# RESISTORS_OLD.net
KiCad netlist of a schematic drawn in Altium Designer
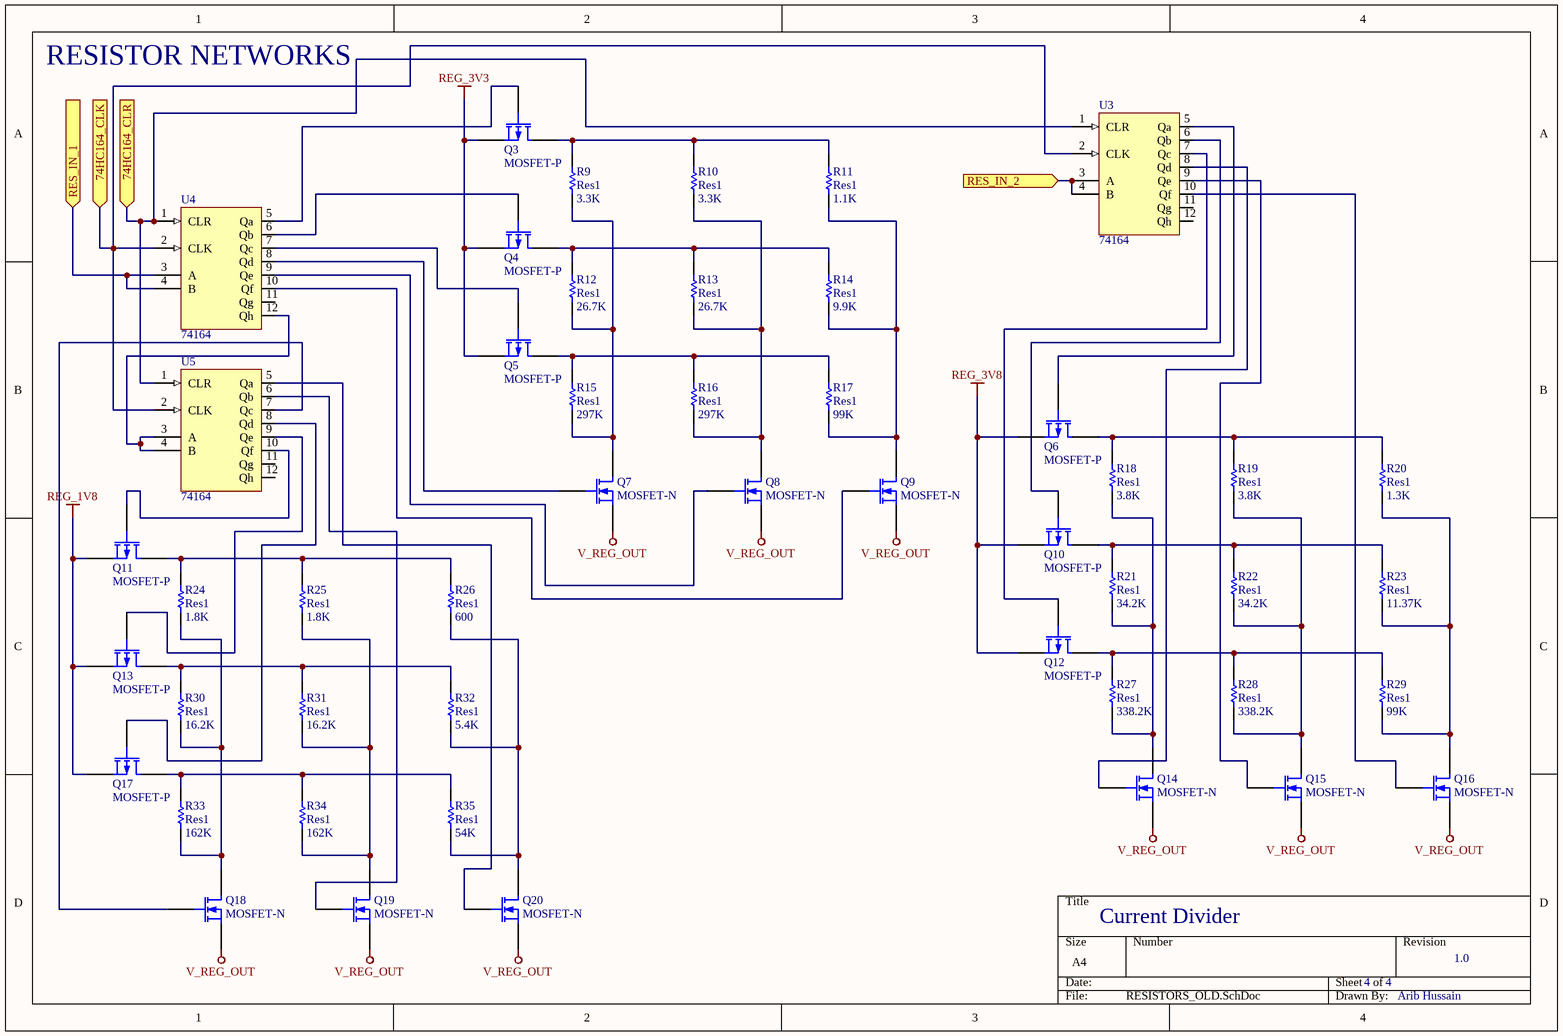
[diagram p0: RESISTORS_OLD.SchDoc]

(export (version "E")
  (design (tool "Eeschema 10.0.6"))
  (components
    (comp (ref "Q3")
      (value "MOSFET-P")
      (footprint "E3")
      (description "P-Channel MOSFET")
      (fields (field (name "PUBLISHER") "Altium Limited"))
      (libsource (lib "Miscellaneous Devices") (part "MOSFET-P"))
    )
    (comp (ref "Q4")
      (value "MOSFET-P")
      (footprint "E3")
      (description "P-Channel MOSFET")
      (fields (field (name "PUBLISHER") "Altium Limited"))
      (libsource (lib "Miscellaneous Devices") (part "MOSFET-P"))
    )
    (comp (ref "Q5")
      (value "MOSFET-P")
      (footprint "E3")
      (description "P-Channel MOSFET")
      (fields (field (name "PUBLISHER") "Altium Limited"))
      (libsource (lib "Miscellaneous Devices") (part "MOSFET-P"))
    )
    (comp (ref "Q6")
      (value "MOSFET-P")
      (footprint "E3")
      (description "P-Channel MOSFET")
      (fields (field (name "PUBLISHER") "Altium Limited"))
      (libsource (lib "Miscellaneous Devices") (part "MOSFET-P"))
    )
    (comp (ref "Q7")
      (value "MOSFET-N")
      (footprint "E3")
      (description "N-Channel MOSFET")
      (fields (field (name "PUBLISHER") "Altium Limited"))
      (libsource (lib "Miscellaneous Devices") (part "MOSFET-N"))
    )
    (comp (ref "Q8")
      (value "MOSFET-N")
      (footprint "E3")
      (description "N-Channel MOSFET")
      (fields (field (name "PUBLISHER") "Altium Limited"))
      (libsource (lib "Miscellaneous Devices") (part "MOSFET-N"))
    )
    (comp (ref "Q9")
      (value "MOSFET-N")
      (footprint "E3")
      (description "N-Channel MOSFET")
      (fields (field (name "PUBLISHER") "Altium Limited"))
      (libsource (lib "Miscellaneous Devices") (part "MOSFET-N"))
    )
    (comp (ref "Q10")
      (value "MOSFET-P")
      (footprint "E3")
      (description "P-Channel MOSFET")
      (fields (field (name "PUBLISHER") "Altium Limited"))
      (libsource (lib "Miscellaneous Devices") (part "MOSFET-P"))
    )
    (comp (ref "Q11")
      (value "MOSFET-P")
      (footprint "E3")
      (description "P-Channel MOSFET")
      (fields (field (name "PUBLISHER") "Altium Limited"))
      (libsource (lib "Miscellaneous Devices") (part "MOSFET-P"))
    )
    (comp (ref "Q12")
      (value "MOSFET-P")
      (footprint "E3")
      (description "P-Channel MOSFET")
      (fields (field (name "PUBLISHER") "Altium Limited"))
      (libsource (lib "Miscellaneous Devices") (part "MOSFET-P"))
    )
    (comp (ref "Q13")
      (value "MOSFET-P")
      (footprint "E3")
      (description "P-Channel MOSFET")
      (fields (field (name "PUBLISHER") "Altium Limited"))
      (libsource (lib "Miscellaneous Devices") (part "MOSFET-P"))
    )
    (comp (ref "Q14")
      (value "MOSFET-N")
      (footprint "E3")
      (description "N-Channel MOSFET")
      (fields (field (name "PUBLISHER") "Altium Limited"))
      (libsource (lib "Miscellaneous Devices") (part "MOSFET-N"))
    )
    (comp (ref "Q15")
      (value "MOSFET-N")
      (footprint "E3")
      (description "N-Channel MOSFET")
      (fields (field (name "PUBLISHER") "Altium Limited"))
      (libsource (lib "Miscellaneous Devices") (part "MOSFET-N"))
    )
    (comp (ref "Q16")
      (value "MOSFET-N")
      (footprint "E3")
      (description "N-Channel MOSFET")
      (fields (field (name "PUBLISHER") "Altium Limited"))
      (libsource (lib "Miscellaneous Devices") (part "MOSFET-N"))
    )
    (comp (ref "Q17")
      (value "MOSFET-P")
      (footprint "E3")
      (description "P-Channel MOSFET")
      (fields (field (name "PUBLISHER") "Altium Limited"))
      (libsource (lib "Miscellaneous Devices") (part "MOSFET-P"))
    )
    (comp (ref "Q18")
      (value "MOSFET-N")
      (footprint "E3")
      (description "N-Channel MOSFET")
      (fields (field (name "PUBLISHER") "Altium Limited"))
      (libsource (lib "Miscellaneous Devices") (part "MOSFET-N"))
    )
    (comp (ref "Q19")
      (value "MOSFET-N")
      (footprint "E3")
      (description "N-Channel MOSFET")
      (fields (field (name "PUBLISHER") "Altium Limited"))
      (libsource (lib "Miscellaneous Devices") (part "MOSFET-N"))
    )
    (comp (ref "Q20")
      (value "MOSFET-N")
      (footprint "E3")
      (description "N-Channel MOSFET")
      (fields (field (name "PUBLISHER") "Altium Limited"))
      (libsource (lib "Miscellaneous Devices") (part "MOSFET-N"))
    )
    (comp (ref "R9")
      (value "Res1")
      (footprint "AXIAL-0.3")
      (description "Resistor")
      (fields (field (name "ALTIUM_VALUE") "3.3K") (field (name "PUBLISHER") "Altium Limited"))
      (libsource (lib "Miscellaneous Devices") (part "Res1"))
    )
    (comp (ref "R10")
      (value "Res1")
      (footprint "AXIAL-0.3")
      (description "Resistor")
      (fields (field (name "ALTIUM_VALUE") "3.3K") (field (name "PUBLISHER") "Altium Limited"))
      (libsource (lib "Miscellaneous Devices") (part "Res1"))
    )
    (comp (ref "R11")
      (value "Res1")
      (footprint "AXIAL-0.3")
      (description "Resistor")
      (fields (field (name "ALTIUM_VALUE") "1.1K") (field (name "PUBLISHER") "Altium Limited"))
      (libsource (lib "Miscellaneous Devices") (part "Res1"))
    )
    (comp (ref "R12")
      (value "Res1")
      (footprint "AXIAL-0.3")
      (description "Resistor")
      (fields (field (name "ALTIUM_VALUE") "26.7K") (field (name "PUBLISHER") "Altium Limited"))
      (libsource (lib "Miscellaneous Devices") (part "Res1"))
    )
    (comp (ref "R13")
      (value "Res1")
      (footprint "AXIAL-0.3")
      (description "Resistor")
      (fields (field (name "ALTIUM_VALUE") "26.7K") (field (name "PUBLISHER") "Altium Limited"))
      (libsource (lib "Miscellaneous Devices") (part "Res1"))
    )
    (comp (ref "R14")
      (value "Res1")
      (footprint "AXIAL-0.3")
      (description "Resistor")
      (fields (field (name "ALTIUM_VALUE") "9.9K") (field (name "PUBLISHER") "Altium Limited"))
      (libsource (lib "Miscellaneous Devices") (part "Res1"))
    )
    (comp (ref "R15")
      (value "Res1")
      (footprint "AXIAL-0.3")
      (description "Resistor")
      (fields (field (name "ALTIUM_VALUE") "297K") (field (name "PUBLISHER") "Altium Limited"))
      (libsource (lib "Miscellaneous Devices") (part "Res1"))
    )
    (comp (ref "R16")
      (value "Res1")
      (footprint "AXIAL-0.3")
      (description "Resistor")
      (fields (field (name "ALTIUM_VALUE") "297K") (field (name "PUBLISHER") "Altium Limited"))
      (libsource (lib "Miscellaneous Devices") (part "Res1"))
    )
    (comp (ref "R17")
      (value "Res1")
      (footprint "AXIAL-0.3")
      (description "Resistor")
      (fields (field (name "ALTIUM_VALUE") "99K") (field (name "PUBLISHER") "Altium Limited"))
      (libsource (lib "Miscellaneous Devices") (part "Res1"))
    )
    (comp (ref "R18")
      (value "Res1")
      (footprint "AXIAL-0.3")
      (description "Resistor")
      (fields (field (name "ALTIUM_VALUE") "3.8K") (field (name "PUBLISHER") "Altium Limited"))
      (libsource (lib "Miscellaneous Devices") (part "Res1"))
    )
    (comp (ref "R19")
      (value "Res1")
      (footprint "AXIAL-0.3")
      (description "Resistor")
      (fields (field (name "ALTIUM_VALUE") "3.8K") (field (name "PUBLISHER") "Altium Limited"))
      (libsource (lib "Miscellaneous Devices") (part "Res1"))
    )
    (comp (ref "R20")
      (value "Res1")
      (footprint "AXIAL-0.3")
      (description "Resistor")
      (fields (field (name "ALTIUM_VALUE") "1.3K") (field (name "PUBLISHER") "Altium Limited"))
      (libsource (lib "Miscellaneous Devices") (part "Res1"))
    )
    (comp (ref "R21")
      (value "Res1")
      (footprint "AXIAL-0.3")
      (description "Resistor")
      (fields (field (name "ALTIUM_VALUE") "34.2K") (field (name "PUBLISHER") "Altium Limited"))
      (libsource (lib "Miscellaneous Devices") (part "Res1"))
    )
    (comp (ref "R22")
      (value "Res1")
      (footprint "AXIAL-0.3")
      (description "Resistor")
      (fields (field (name "ALTIUM_VALUE") "34.2K") (field (name "PUBLISHER") "Altium Limited"))
      (libsource (lib "Miscellaneous Devices") (part "Res1"))
    )
    (comp (ref "R23")
      (value "Res1")
      (footprint "AXIAL-0.3")
      (description "Resistor")
      (fields (field (name "ALTIUM_VALUE") "11.37K") (field (name "PUBLISHER") "Altium Limited"))
      (libsource (lib "Miscellaneous Devices") (part "Res1"))
    )
    (comp (ref "R24")
      (value "Res1")
      (footprint "AXIAL-0.3")
      (description "Resistor")
      (fields (field (name "ALTIUM_VALUE") "1.8K") (field (name "PUBLISHER") "Altium Limited"))
      (libsource (lib "Miscellaneous Devices") (part "Res1"))
    )
    (comp (ref "R25")
      (value "Res1")
      (footprint "AXIAL-0.3")
      (description "Resistor")
      (fields (field (name "ALTIUM_VALUE") "1.8K") (field (name "PUBLISHER") "Altium Limited"))
      (libsource (lib "Miscellaneous Devices") (part "Res1"))
    )
    (comp (ref "R26")
      (value "Res1")
      (footprint "AXIAL-0.3")
      (description "Resistor")
      (fields (field (name "ALTIUM_VALUE") "600") (field (name "PUBLISHER") "Altium Limited"))
      (libsource (lib "Miscellaneous Devices") (part "Res1"))
    )
    (comp (ref "R27")
      (value "Res1")
      (footprint "AXIAL-0.3")
      (description "Resistor")
      (fields (field (name "ALTIUM_VALUE") "338.2K") (field (name "PUBLISHER") "Altium Limited"))
      (libsource (lib "Miscellaneous Devices") (part "Res1"))
    )
    (comp (ref "R28")
      (value "Res1")
      (footprint "AXIAL-0.3")
      (description "Resistor")
      (fields (field (name "ALTIUM_VALUE") "338.2K") (field (name "PUBLISHER") "Altium Limited"))
      (libsource (lib "Miscellaneous Devices") (part "Res1"))
    )
    (comp (ref "R29")
      (value "Res1")
      (footprint "AXIAL-0.3")
      (description "Resistor")
      (fields (field (name "ALTIUM_VALUE") "99K") (field (name "PUBLISHER") "Altium Limited"))
      (libsource (lib "Miscellaneous Devices") (part "Res1"))
    )
    (comp (ref "R30")
      (value "Res1")
      (footprint "AXIAL-0.3")
      (description "Resistor")
      (fields (field (name "ALTIUM_VALUE") "16.2K") (field (name "PUBLISHER") "Altium Limited"))
      (libsource (lib "Miscellaneous Devices") (part "Res1"))
    )
    (comp (ref "R31")
      (value "Res1")
      (footprint "AXIAL-0.3")
      (description "Resistor")
      (fields (field (name "ALTIUM_VALUE") "16.2K") (field (name "PUBLISHER") "Altium Limited"))
      (libsource (lib "Miscellaneous Devices") (part "Res1"))
    )
    (comp (ref "R32")
      (value "Res1")
      (footprint "AXIAL-0.3")
      (description "Resistor")
      (fields (field (name "ALTIUM_VALUE") "5.4K") (field (name "PUBLISHER") "Altium Limited"))
      (libsource (lib "Miscellaneous Devices") (part "Res1"))
    )
    (comp (ref "R33")
      (value "Res1")
      (footprint "AXIAL-0.3")
      (description "Resistor")
      (fields (field (name "ALTIUM_VALUE") "162K") (field (name "PUBLISHER") "Altium Limited"))
      (libsource (lib "Miscellaneous Devices") (part "Res1"))
    )
    (comp (ref "R34")
      (value "Res1")
      (footprint "AXIAL-0.3")
      (description "Resistor")
      (fields (field (name "ALTIUM_VALUE") "162K") (field (name "PUBLISHER") "Altium Limited"))
      (libsource (lib "Miscellaneous Devices") (part "Res1"))
    )
    (comp (ref "R35")
      (value "Res1")
      (footprint "AXIAL-0.3")
      (description "Resistor")
      (fields (field (name "ALTIUM_VALUE") "54K") (field (name "PUBLISHER") "Altium Limited"))
      (libsource (lib "Miscellaneous Devices") (part "Res1"))
    )
    (comp (ref "U3")
      (value "74164")
      (description "8-Bit Shift Register")
      (libsource (lib "main_schlib") (part "74HC164"))
    )
    (comp (ref "U4")
      (value "74164")
      (description "8-Bit Shift Register")
      (libsource (lib "main_schlib") (part "74HC164"))
    )
    (comp (ref "U5")
      (value "74164")
      (description "8-Bit Shift Register")
      (libsource (lib "main_schlib") (part "74HC164"))
    )
  )
  (nets
    (net (code "1") (name "/74HC164_CLK") (class "Default")
      (node (ref "U3") (pin "2") (pinfunction "CLK_2") (pintype "input"))
      (node (ref "U4") (pin "2") (pinfunction "CLK_2") (pintype "input"))
      (node (ref "U5") (pin "2") (pinfunction "CLK_2") (pintype "input"))
    )
    (net (code "2") (name "/74HC164_CLR") (class "Default")
      (node (ref "U3") (pin "1") (pinfunction "CLR_1") (pintype "input"))
      (node (ref "U4") (pin "1") (pinfunction "CLR_1") (pintype "input"))
      (node (ref "U5") (pin "1") (pinfunction "CLR_1") (pintype "input"))
    )
    (net (code "3") (name "/RES_IN_1") (class "Default")
      (node (ref "U4") (pin "3") (pinfunction "A_3") (pintype "passive"))
      (node (ref "U4") (pin "4") (pinfunction "B_4") (pintype "passive"))
    )
    (net (code "4") (name "/RES_IN_2") (class "Default")
      (node (ref "U3") (pin "3") (pinfunction "A_3") (pintype "passive"))
      (node (ref "U3") (pin "4") (pinfunction "B_4") (pintype "passive"))
    )
    (net (code "5") (name "Net-(Q3-D)") (class "Default")
      (node (ref "Q3") (pin "1") (pinfunction "D_1") (pintype "passive"))
      (node (ref "R10") (pin "2") (pinfunction "2_2") (pintype "passive"))
      (node (ref "R11") (pin "2") (pinfunction "2_2") (pintype "passive"))
      (node (ref "R9") (pin "2") (pinfunction "2_2") (pintype "passive"))
    )
    (net (code "6") (name "Net-(Q3-G)") (class "Default")
      (node (ref "Q3") (pin "2") (pinfunction "G_2") (pintype "passive"))
      (node (ref "U4") (pin "5") (pinfunction "Qa_5") (pintype "passive"))
    )
    (net (code "7") (name "Net-(Q4-D)") (class "Default")
      (node (ref "Q4") (pin "1") (pinfunction "D_1") (pintype "passive"))
      (node (ref "R12") (pin "2") (pinfunction "2_2") (pintype "passive"))
      (node (ref "R13") (pin "2") (pinfunction "2_2") (pintype "passive"))
      (node (ref "R14") (pin "2") (pinfunction "2_2") (pintype "passive"))
    )
    (net (code "8") (name "Net-(Q4-G)") (class "Default")
      (node (ref "Q4") (pin "2") (pinfunction "G_2") (pintype "passive"))
      (node (ref "U4") (pin "6") (pinfunction "Qb_6") (pintype "passive"))
    )
    (net (code "9") (name "Net-(Q5-D)") (class "Default")
      (node (ref "Q5") (pin "1") (pinfunction "D_1") (pintype "passive"))
      (node (ref "R15") (pin "2") (pinfunction "2_2") (pintype "passive"))
      (node (ref "R16") (pin "2") (pinfunction "2_2") (pintype "passive"))
      (node (ref "R17") (pin "2") (pinfunction "2_2") (pintype "passive"))
    )
    (net (code "10") (name "Net-(Q5-G)") (class "Default")
      (node (ref "Q5") (pin "2") (pinfunction "G_2") (pintype "passive"))
      (node (ref "U4") (pin "7") (pinfunction "Qc_7") (pintype "passive"))
    )
    (net (code "11") (name "Net-(Q6-D)") (class "Default")
      (node (ref "Q6") (pin "1") (pinfunction "D_1") (pintype "passive"))
      (node (ref "R18") (pin "2") (pinfunction "2_2") (pintype "passive"))
      (node (ref "R19") (pin "2") (pinfunction "2_2") (pintype "passive"))
      (node (ref "R20") (pin "2") (pinfunction "2_2") (pintype "passive"))
    )
    (net (code "12") (name "Net-(Q6-G)") (class "Default")
      (node (ref "Q6") (pin "2") (pinfunction "G_2") (pintype "passive"))
      (node (ref "U3") (pin "5") (pinfunction "Qa_5") (pintype "passive"))
    )
    (net (code "13") (name "Net-(Q7-D)") (class "Default")
      (node (ref "Q7") (pin "1") (pinfunction "D_1") (pintype "passive"))
      (node (ref "R12") (pin "1") (pinfunction "1_1") (pintype "passive"))
      (node (ref "R15") (pin "1") (pinfunction "1_1") (pintype "passive"))
      (node (ref "R9") (pin "1") (pinfunction "1_1") (pintype "passive"))
    )
    (net (code "14") (name "Net-(Q7-G)") (class "Default")
      (node (ref "Q7") (pin "2") (pinfunction "G_2") (pintype "passive"))
      (node (ref "U4") (pin "8") (pinfunction "Qd_8") (pintype "passive"))
    )
    (net (code "15") (name "Net-(Q8-D)") (class "Default")
      (node (ref "Q8") (pin "1") (pinfunction "D_1") (pintype "passive"))
      (node (ref "R10") (pin "1") (pinfunction "1_1") (pintype "passive"))
      (node (ref "R13") (pin "1") (pinfunction "1_1") (pintype "passive"))
      (node (ref "R16") (pin "1") (pinfunction "1_1") (pintype "passive"))
    )
    (net (code "16") (name "Net-(Q8-G)") (class "Default")
      (node (ref "Q8") (pin "2") (pinfunction "G_2") (pintype "passive"))
      (node (ref "U4") (pin "9") (pinfunction "Qe_9") (pintype "passive"))
    )
    (net (code "17") (name "Net-(Q9-D)") (class "Default")
      (node (ref "Q9") (pin "1") (pinfunction "D_1") (pintype "passive"))
      (node (ref "R11") (pin "1") (pinfunction "1_1") (pintype "passive"))
      (node (ref "R14") (pin "1") (pinfunction "1_1") (pintype "passive"))
      (node (ref "R17") (pin "1") (pinfunction "1_1") (pintype "passive"))
    )
    (net (code "18") (name "Net-(Q9-G)") (class "Default")
      (node (ref "Q9") (pin "2") (pinfunction "G_2") (pintype "passive"))
      (node (ref "U4") (pin "10") (pinfunction "Qf_10") (pintype "passive"))
    )
    (net (code "19") (name "Net-(Q10-D)") (class "Default")
      (node (ref "Q10") (pin "1") (pinfunction "D_1") (pintype "passive"))
      (node (ref "R21") (pin "2") (pinfunction "2_2") (pintype "passive"))
      (node (ref "R22") (pin "2") (pinfunction "2_2") (pintype "passive"))
      (node (ref "R23") (pin "2") (pinfunction "2_2") (pintype "passive"))
    )
    (net (code "20") (name "Net-(Q10-G)") (class "Default")
      (node (ref "Q10") (pin "2") (pinfunction "G_2") (pintype "passive"))
      (node (ref "U3") (pin "6") (pinfunction "Qb_6") (pintype "passive"))
    )
    (net (code "21") (name "Net-(Q11-D)") (class "Default")
      (node (ref "Q11") (pin "1") (pinfunction "D_1") (pintype "passive"))
      (node (ref "R24") (pin "2") (pinfunction "2_2") (pintype "passive"))
      (node (ref "R25") (pin "2") (pinfunction "2_2") (pintype "passive"))
      (node (ref "R26") (pin "2") (pinfunction "2_2") (pintype "passive"))
    )
    (net (code "22") (name "Net-(Q11-G)") (class "Default")
      (node (ref "Q11") (pin "2") (pinfunction "G_2") (pintype "passive"))
      (node (ref "U5") (pin "10") (pinfunction "Qf_10") (pintype "passive"))
    )
    (net (code "23") (name "Net-(Q12-D)") (class "Default")
      (node (ref "Q12") (pin "1") (pinfunction "D_1") (pintype "passive"))
      (node (ref "R27") (pin "2") (pinfunction "2_2") (pintype "passive"))
      (node (ref "R28") (pin "2") (pinfunction "2_2") (pintype "passive"))
      (node (ref "R29") (pin "2") (pinfunction "2_2") (pintype "passive"))
    )
    (net (code "24") (name "Net-(Q12-G)") (class "Default")
      (node (ref "Q12") (pin "2") (pinfunction "G_2") (pintype "passive"))
      (node (ref "U3") (pin "7") (pinfunction "Qc_7") (pintype "passive"))
    )
    (net (code "25") (name "Net-(Q13-D)") (class "Default")
      (node (ref "Q13") (pin "1") (pinfunction "D_1") (pintype "passive"))
      (node (ref "R30") (pin "2") (pinfunction "2_2") (pintype "passive"))
      (node (ref "R31") (pin "2") (pinfunction "2_2") (pintype "passive"))
      (node (ref "R32") (pin "2") (pinfunction "2_2") (pintype "passive"))
    )
    (net (code "26") (name "Net-(Q13-G)") (class "Default")
      (node (ref "Q13") (pin "2") (pinfunction "G_2") (pintype "passive"))
      (node (ref "U5") (pin "9") (pinfunction "Qe_9") (pintype "passive"))
    )
    (net (code "27") (name "Net-(Q14-D)") (class "Default")
      (node (ref "Q14") (pin "1") (pinfunction "D_1") (pintype "passive"))
      (node (ref "R18") (pin "1") (pinfunction "1_1") (pintype "passive"))
      (node (ref "R21") (pin "1") (pinfunction "1_1") (pintype "passive"))
      (node (ref "R27") (pin "1") (pinfunction "1_1") (pintype "passive"))
    )
    (net (code "28") (name "Net-(Q14-G)") (class "Default")
      (node (ref "Q14") (pin "2") (pinfunction "G_2") (pintype "passive"))
      (node (ref "U3") (pin "8") (pinfunction "Qd_8") (pintype "passive"))
    )
    (net (code "29") (name "Net-(Q15-D)") (class "Default")
      (node (ref "Q15") (pin "1") (pinfunction "D_1") (pintype "passive"))
      (node (ref "R19") (pin "1") (pinfunction "1_1") (pintype "passive"))
      (node (ref "R22") (pin "1") (pinfunction "1_1") (pintype "passive"))
      (node (ref "R28") (pin "1") (pinfunction "1_1") (pintype "passive"))
    )
    (net (code "30") (name "Net-(Q15-G)") (class "Default")
      (node (ref "Q15") (pin "2") (pinfunction "G_2") (pintype "passive"))
      (node (ref "U3") (pin "9") (pinfunction "Qe_9") (pintype "passive"))
    )
    (net (code "31") (name "Net-(Q16-D)") (class "Default")
      (node (ref "Q16") (pin "1") (pinfunction "D_1") (pintype "passive"))
      (node (ref "R20") (pin "1") (pinfunction "1_1") (pintype "passive"))
      (node (ref "R23") (pin "1") (pinfunction "1_1") (pintype "passive"))
      (node (ref "R29") (pin "1") (pinfunction "1_1") (pintype "passive"))
    )
    (net (code "32") (name "Net-(Q16-G)") (class "Default")
      (node (ref "Q16") (pin "2") (pinfunction "G_2") (pintype "passive"))
      (node (ref "U3") (pin "10") (pinfunction "Qf_10") (pintype "passive"))
    )
    (net (code "33") (name "Net-(Q17-D)") (class "Default")
      (node (ref "Q17") (pin "1") (pinfunction "D_1") (pintype "passive"))
      (node (ref "R33") (pin "2") (pinfunction "2_2") (pintype "passive"))
      (node (ref "R34") (pin "2") (pinfunction "2_2") (pintype "passive"))
      (node (ref "R35") (pin "2") (pinfunction "2_2") (pintype "passive"))
    )
    (net (code "34") (name "Net-(Q17-G)") (class "Default")
      (node (ref "Q17") (pin "2") (pinfunction "G_2") (pintype "passive"))
      (node (ref "U5") (pin "8") (pinfunction "Qd_8") (pintype "passive"))
    )
    (net (code "35") (name "Net-(Q18-D)") (class "Default")
      (node (ref "Q18") (pin "1") (pinfunction "D_1") (pintype "passive"))
      (node (ref "R24") (pin "1") (pinfunction "1_1") (pintype "passive"))
      (node (ref "R30") (pin "1") (pinfunction "1_1") (pintype "passive"))
      (node (ref "R33") (pin "1") (pinfunction "1_1") (pintype "passive"))
    )
    (net (code "36") (name "Net-(Q18-G)") (class "Default")
      (node (ref "Q18") (pin "2") (pinfunction "G_2") (pintype "passive"))
      (node (ref "U5") (pin "7") (pinfunction "Qc_7") (pintype "passive"))
    )
    (net (code "37") (name "Net-(Q19-D)") (class "Default")
      (node (ref "Q19") (pin "1") (pinfunction "D_1") (pintype "passive"))
      (node (ref "R25") (pin "1") (pinfunction "1_1") (pintype "passive"))
      (node (ref "R31") (pin "1") (pinfunction "1_1") (pintype "passive"))
      (node (ref "R34") (pin "1") (pinfunction "1_1") (pintype "passive"))
    )
    (net (code "38") (name "Net-(Q19-G)") (class "Default")
      (node (ref "Q19") (pin "2") (pinfunction "G_2") (pintype "passive"))
      (node (ref "U5") (pin "6") (pinfunction "Qb_6") (pintype "passive"))
    )
    (net (code "39") (name "Net-(Q20-D)") (class "Default")
      (node (ref "Q20") (pin "1") (pinfunction "D_1") (pintype "passive"))
      (node (ref "R26") (pin "1") (pinfunction "1_1") (pintype "passive"))
      (node (ref "R32") (pin "1") (pinfunction "1_1") (pintype "passive"))
      (node (ref "R35") (pin "1") (pinfunction "1_1") (pintype "passive"))
    )
    (net (code "40") (name "Net-(Q20-G)") (class "Default")
      (node (ref "Q20") (pin "2") (pinfunction "G_2") (pintype "passive"))
      (node (ref "U5") (pin "5") (pinfunction "Qa_5") (pintype "passive"))
    )
    (net (code "41") (name "Net-(U4-Qh)") (class "Default")
      (node (ref "U4") (pin "12") (pinfunction "Qh_12") (pintype "passive"))
      (node (ref "U5") (pin "3") (pinfunction "A_3") (pintype "passive"))
      (node (ref "U5") (pin "4") (pinfunction "B_4") (pintype "passive"))
    )
    (net (code "42") (name "REG_1V8") (class "Default")
      (node (ref "Q11") (pin "3") (pinfunction "S_3") (pintype "passive"))
      (node (ref "Q13") (pin "3") (pinfunction "S_3") (pintype "passive"))
      (node (ref "Q17") (pin "3") (pinfunction "S_3") (pintype "passive"))
    )
    (net (code "43") (name "REG_3V3") (class "Default")
      (node (ref "Q3") (pin "3") (pinfunction "S_3") (pintype "passive"))
      (node (ref "Q4") (pin "3") (pinfunction "S_3") (pintype "passive"))
      (node (ref "Q5") (pin "3") (pinfunction "S_3") (pintype "passive"))
    )
    (net (code "44") (name "REG_3V8") (class "Default")
      (node (ref "Q10") (pin "3") (pinfunction "S_3") (pintype "passive"))
      (node (ref "Q12") (pin "3") (pinfunction "S_3") (pintype "passive"))
      (node (ref "Q6") (pin "3") (pinfunction "S_3") (pintype "passive"))
    )
    (net (code "45") (name "V_REG_OUT") (class "Default")
      (node (ref "Q14") (pin "3") (pinfunction "S_3") (pintype "passive"))
      (node (ref "Q15") (pin "3") (pinfunction "S_3") (pintype "passive"))
      (node (ref "Q16") (pin "3") (pinfunction "S_3") (pintype "passive"))
      (node (ref "Q18") (pin "3") (pinfunction "S_3") (pintype "passive"))
      (node (ref "Q19") (pin "3") (pinfunction "S_3") (pintype "passive"))
      (node (ref "Q20") (pin "3") (pinfunction "S_3") (pintype "passive"))
      (node (ref "Q7") (pin "3") (pinfunction "S_3") (pintype "passive"))
      (node (ref "Q8") (pin "3") (pinfunction "S_3") (pintype "passive"))
      (node (ref "Q9") (pin "3") (pinfunction "S_3") (pintype "passive"))
    )
    (net (code "46") (name "unconnected-(U3-Qg-Pad11)") (class "Default")
      (node (ref "U3") (pin "11") (pinfunction "Qg_11") (pintype "passive"))
    )
    (net (code "47") (name "unconnected-(U3-Qh-Pad12)") (class "Default")
      (node (ref "U3") (pin "12") (pinfunction "Qh_12") (pintype "passive"))
    )
    (net (code "48") (name "unconnected-(U4-Qg-Pad11)") (class "Default")
      (node (ref "U4") (pin "11") (pinfunction "Qg_11") (pintype "passive"))
    )
    (net (code "49") (name "unconnected-(U5-Qg-Pad11)") (class "Default")
      (node (ref "U5") (pin "11") (pinfunction "Qg_11") (pintype "passive"))
    )
    (net (code "50") (name "unconnected-(U5-Qh-Pad12)") (class "Default")
      (node (ref "U5") (pin "12") (pinfunction "Qh_12") (pintype "passive"))
    )
  )
)
